# Power_Neg.net
KiCad netlist of a schematic drawn in Altium Designer
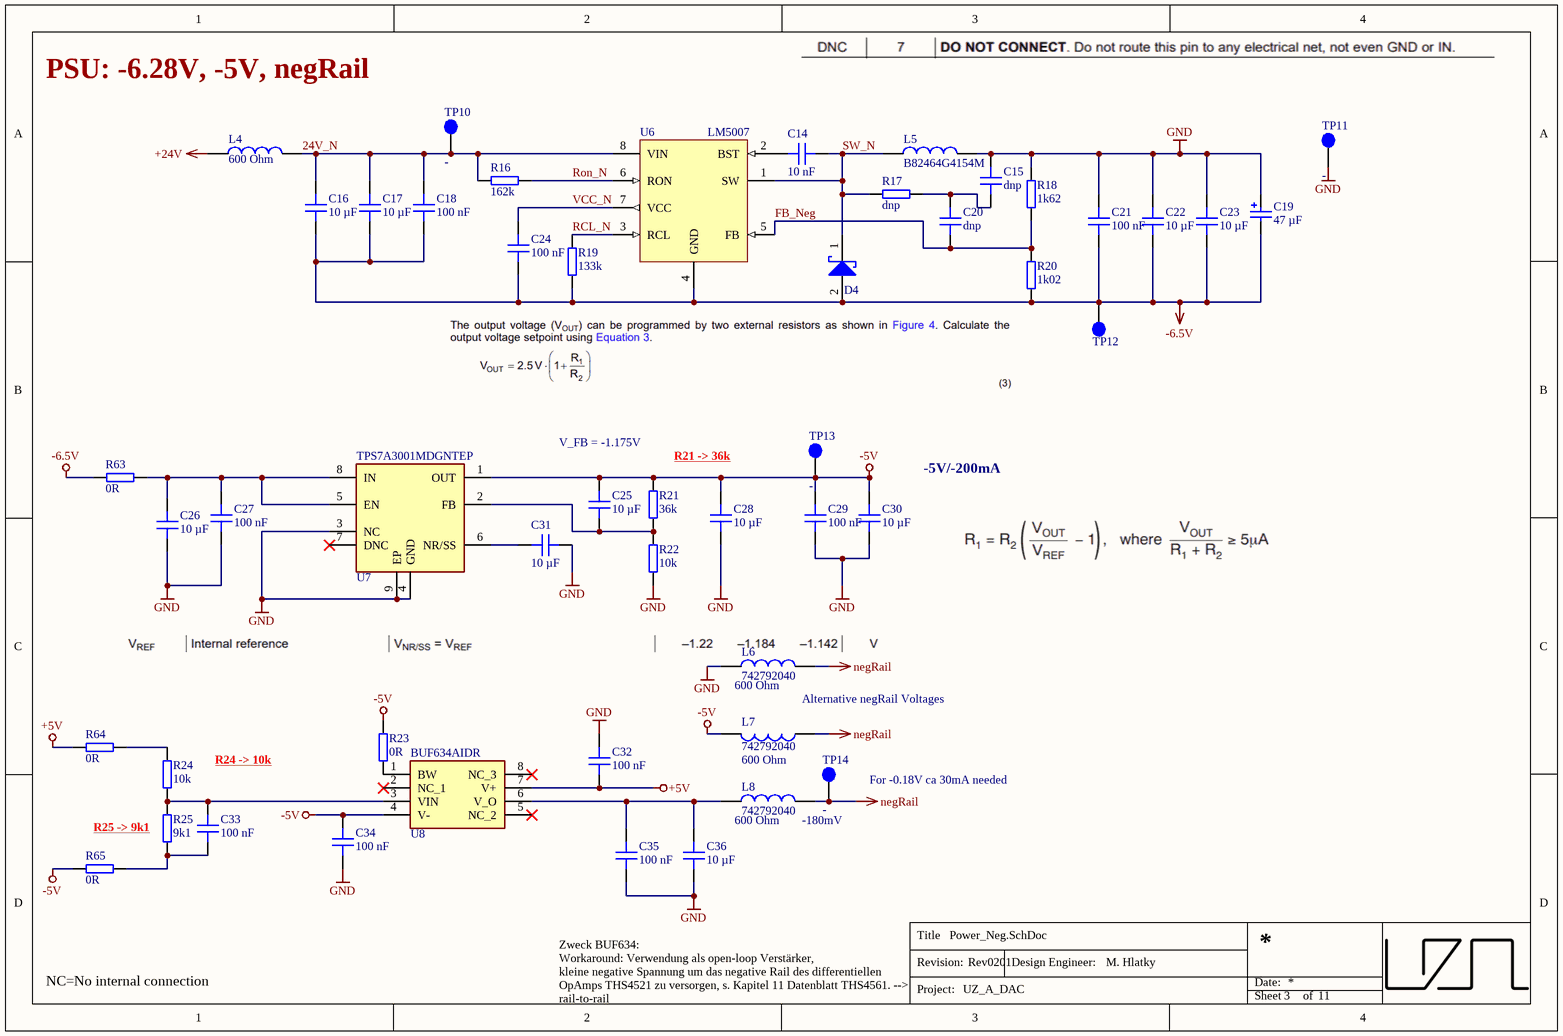
[diagram p0: Power_Neg.SchDoc]

(export (version "E")
  (design (tool "Eeschema 10.0.6"))
  (components
    (comp (ref "C14")
      (value "10 nF")
      (footprint "C_0603")
      (description "Capacitor 0603, 25 VDC, 10 nF, X7R")
      (fields
        (field (name "MANUFACTURER PART NUMBER") "885012206065")
        (field (name "MANUFACTURER") "Wurth Elektronik")
        (field (name "CREATED FROM") "MGremer")
      )
      (libsource (lib "user") (part "Capacitor"))
    )
    (comp (ref "C15")
      (value "dnp")
      (footprint "C_1206")
      (description "Capacitor 1206, 50 VDC, 0.027 µF, C0G")
      (fields
        (field (name "MANUFACTURER PART NUMBER") "GRM3195C1H273JA01D")
        (field (name "MANUFACTURER") "Murata Electronics")
        (field (name "CREATED FROM") "MGremer")
      )
      (libsource (lib "user") (part "Capacitor"))
    )
    (comp (ref "C16")
      (value "10 µF")
      (footprint "C_1206")
      (description "Capacitor 1206, 50 VDC, 10 µF, X5R")
      (fields
        (field (name "MANUFACTURER PART NUMBER") "GRT31CR61H106KE01L")
        (field (name "MANUFACTURER") "Murata Electronics")
        (field (name "CREATED FROM") "MGremer")
      )
      (libsource (lib "user") (part "Capacitor"))
    )
    (comp (ref "C17")
      (value "10 µF")
      (footprint "C_1206")
      (description "Capacitor 1206, 50 VDC, 10 µF, X5R")
      (fields
        (field (name "MANUFACTURER PART NUMBER") "GRT31CR61H106KE01L")
        (field (name "MANUFACTURER") "Murata Electronics")
        (field (name "CREATED FROM") "MGremer")
      )
      (libsource (lib "user") (part "Capacitor"))
    )
    (comp (ref "C18")
      (value "100 nF")
      (footprint "C_0603")
      (description "Capacitor 0603, 6.3 VDC, 100 nF, X5R")
      (fields
        (field (name "MANUFACTURER PART NUMBER") "C0603C104K9PACTU")
        (field (name "MANUFACTURER") "KEMET")
        (field (name "CREATED FROM") "MGremer")
      )
      (libsource (lib "user") (part "Capacitor"))
    )
    (comp (ref "C19")
      (value "47 µF")
      (footprint "WCAP-ASLI_5x5.5")
      (description "Capacitor WCAP, 6.3 VDC, 100 µF")
      (fields
        (field (name "MANUFACTURER PART NUMBER") "865080242004")
        (field (name "MANUFACTURER") "Wuerth Elektronik")
        (field (name "CREATED FROM") "MHlatky")
      )
      (libsource (lib "user") (part "Capacitor_Polarized"))
    )
    (comp (ref "C20")
      (value "dnp")
      (footprint "C_1206")
      (description "Capacitor 1206, 50 VDC, 0.027 µF, C0G")
      (fields
        (field (name "MANUFACTURER PART NUMBER") "GRM3195C1H273JA01D")
        (field (name "MANUFACTURER") "Murata Electronics")
        (field (name "CREATED FROM") "MGremer")
      )
      (libsource (lib "user") (part "Capacitor"))
    )
    (comp (ref "C21")
      (value "100 nF")
      (footprint "C_0603")
      (description "Capacitor 0603, 6.3 VDC, 100 nF, X5R")
      (fields
        (field (name "MANUFACTURER PART NUMBER") "C0603C104K9PACTU")
        (field (name "MANUFACTURER") "KEMET")
        (field (name "CREATED FROM") "MGremer")
      )
      (libsource (lib "user") (part "Capacitor"))
    )
    (comp (ref "C22")
      (value "10 µF")
      (footprint "C_1206")
      (description "Capacitor 1206, 50 VDC, 10 µF, X5R")
      (fields
        (field (name "MANUFACTURER PART NUMBER") "GRT31CR61H106KE01L")
        (field (name "MANUFACTURER") "Murata Electronics")
        (field (name "CREATED FROM") "MGremer")
      )
      (libsource (lib "user") (part "Capacitor"))
    )
    (comp (ref "C23")
      (value "10 µF")
      (footprint "C_1206")
      (description "Capacitor 1206, 50 VDC, 10 µF, X5R")
      (fields
        (field (name "MANUFACTURER PART NUMBER") "GRT31CR61H106KE01L")
        (field (name "MANUFACTURER") "Murata Electronics")
        (field (name "CREATED FROM") "MGremer")
      )
      (libsource (lib "user") (part "Capacitor"))
    )
    (comp (ref "C24")
      (value "100 nF")
      (footprint "C_0603")
      (description "Capacitor 0603, 6.3 VDC, 100 nF, X5R")
      (fields
        (field (name "MANUFACTURER PART NUMBER") "C0603C104K9PACTU")
        (field (name "MANUFACTURER") "KEMET")
        (field (name "CREATED FROM") "MGremer")
      )
      (libsource (lib "user") (part "Capacitor"))
    )
    (comp (ref "C25")
      (value "10 µF")
      (footprint "C_1206")
      (description "Capacitor 1206, 50 VDC, 10 µF, X5R")
      (fields
        (field (name "MANUFACTURER PART NUMBER") "GRT31CR61H106KE01L")
        (field (name "MANUFACTURER") "Murata Electronics")
        (field (name "CREATED FROM") "MGremer")
      )
      (libsource (lib "user") (part "Capacitor"))
    )
    (comp (ref "C26")
      (value "10 µF")
      (footprint "C_1206")
      (description "Capacitor 1206, 50 VDC, 10 µF, X5R")
      (fields
        (field (name "MANUFACTURER PART NUMBER") "GRT31CR61H106KE01L")
        (field (name "MANUFACTURER") "Murata Electronics")
        (field (name "CREATED FROM") "MGremer")
      )
      (libsource (lib "user") (part "Capacitor"))
    )
    (comp (ref "C27")
      (value "100 nF")
      (footprint "C_0603")
      (description "Capacitor 0603, 6.3 VDC, 100 nF, X5R")
      (fields
        (field (name "MANUFACTURER PART NUMBER") "C0603C104K9PACTU")
        (field (name "MANUFACTURER") "KEMET")
        (field (name "CREATED FROM") "MGremer")
      )
      (libsource (lib "user") (part "Capacitor"))
    )
    (comp (ref "C28")
      (value "10 µF")
      (footprint "C_1206")
      (description "Capacitor 1206, 50 VDC, 10 µF, X5R")
      (fields
        (field (name "MANUFACTURER PART NUMBER") "GRT31CR61H106KE01L")
        (field (name "MANUFACTURER") "Murata Electronics")
        (field (name "CREATED FROM") "MGremer")
      )
      (libsource (lib "user") (part "Capacitor"))
    )
    (comp (ref "C29")
      (value "100 nF")
      (footprint "C_0603")
      (description "Capacitor 0603, 6.3 VDC, 100 nF, X5R")
      (fields
        (field (name "MANUFACTURER PART NUMBER") "C0603C104K9PACTU")
        (field (name "MANUFACTURER") "KEMET")
        (field (name "CREATED FROM") "MGremer")
      )
      (libsource (lib "user") (part "Capacitor"))
    )
    (comp (ref "C30")
      (value "10 µF")
      (footprint "C_1206")
      (description "Capacitor 1206, 50 VDC, 10 µF, X5R")
      (fields
        (field (name "MANUFACTURER PART NUMBER") "GRT31CR61H106KE01L")
        (field (name "MANUFACTURER") "Murata Electronics")
        (field (name "CREATED FROM") "MGremer")
      )
      (libsource (lib "user") (part "Capacitor"))
    )
    (comp (ref "C31")
      (value "10 µF")
      (footprint "C_1206")
      (description "Capacitor 1206, 50 VDC, 10 µF, X5R")
      (fields
        (field (name "MANUFACTURER PART NUMBER") "GRT31CR61H106KE01L")
        (field (name "MANUFACTURER") "Murata Electronics")
        (field (name "CREATED FROM") "MGremer")
      )
      (libsource (lib "user") (part "Capacitor"))
    )
    (comp (ref "C32")
      (value "100 nF")
      (footprint "C_0603")
      (description "Capacitor 0603, 6.3 VDC, 100 nF, X5R")
      (fields
        (field (name "MANUFACTURER PART NUMBER") "C0603C104K9PACTU")
        (field (name "MANUFACTURER") "KEMET")
        (field (name "CREATED FROM") "MGremer")
      )
      (libsource (lib "user") (part "Capacitor"))
    )
    (comp (ref "C33")
      (value "100 nF")
      (footprint "C_0603")
      (description "Capacitor 0603, 6.3 VDC, 100 nF, X5R")
      (fields
        (field (name "MANUFACTURER PART NUMBER") "C0603C104K9PACTU")
        (field (name "MANUFACTURER") "KEMET")
        (field (name "CREATED FROM") "MGremer")
      )
      (libsource (lib "user") (part "Capacitor"))
    )
    (comp (ref "C34")
      (value "100 nF")
      (footprint "C_0603")
      (description "Capacitor 0603, 6.3 VDC, 100 nF, X5R")
      (fields
        (field (name "MANUFACTURER PART NUMBER") "C0603C104K9PACTU")
        (field (name "MANUFACTURER") "KEMET")
        (field (name "CREATED FROM") "MGremer")
      )
      (libsource (lib "user") (part "Capacitor"))
    )
    (comp (ref "C35")
      (value "100 nF")
      (footprint "C_0603")
      (description "Capacitor 0603, 6.3 VDC, 100 nF, X5R")
      (fields
        (field (name "MANUFACTURER PART NUMBER") "C0603C104K9PACTU")
        (field (name "MANUFACTURER") "KEMET")
        (field (name "CREATED FROM") "MGremer")
      )
      (libsource (lib "user") (part "Capacitor"))
    )
    (comp (ref "C36")
      (value "10 µF")
      (footprint "C_1206")
      (description "Capacitor 1206, 50 VDC, 10 µF, X5R")
      (fields
        (field (name "MANUFACTURER PART NUMBER") "GRT31CR61H106KE01L")
        (field (name "MANUFACTURER") "Murata Electronics")
        (field (name "CREATED FROM") "MGremer")
      )
      (libsource (lib "user") (part "Capacitor"))
    )
    (comp (ref "D4")
      (value "BYS12-90-E3/TR3")
      (footprint "DIOM4227X23N")
      (description "Schottky Rectifier, 1.5 A, 90 V")
      (fields
        (field (name "MANUFACTURER") "Vishay General Semiconductor")
        (field (name "CREATED FROM") "MGremer")
      )
      (libsource (lib "user") (part "STPS340-Y"))
    )
    (comp (ref "L4")
      (value "600 Ohm")
      (footprint "WE-CBF_0805_High Current")
      (description "Inductance, 0805, 100 MHz, 600 Ohm, 2 A")
      (fields
        (field (name "MANUFACTURER PART NUMBER") "742792040")
        (field (name "MANUFACTURER") "Wurth Elektronik")
        (field (name "CREATED FROM") "MGremer")
      )
      (libsource (lib "user") (part "WE-CBF"))
    )
    (comp (ref "L5")
      (value "B82464G4154M")
      (footprint "SMT_inductor_1050")
      (description "Inductor SMT, 10 x 10, 150 µH, 0.8 A")
      (fields
        (field (name "MF") "EPCOS / TDK")
        (field (name "MANUFACTURER") "TDK")
        (field (name "CREATED FROM") "MGremer")
      )
      (libsource (lib "user") (part "B82464G4154M"))
    )
    (comp (ref "L6")
      (value "742792040")
      (footprint "WE-CBF_0805_High Current")
      (description "Inductance, 0805, 100 MHz, 600 Ohm, 2 A")
      (fields
        (field (name "MANUFACTURER") "Wurth Elektronik")
        (field (name "ALTIUM_VALUE") "600 Ohm")
        (field (name "CREATED FROM") "MGremer")
      )
      (libsource (lib "user") (part "WE-CBF"))
    )
    (comp (ref "L7")
      (value "742792040")
      (footprint "WE-CBF_0805_High Current")
      (description "Inductance, 0805, 100 MHz, 600 Ohm, 2 A")
      (fields
        (field (name "MANUFACTURER") "Wurth Elektronik")
        (field (name "ALTIUM_VALUE") "600 Ohm")
        (field (name "CREATED FROM") "MGremer")
      )
      (libsource (lib "user") (part "WE-CBF"))
    )
    (comp (ref "L8")
      (value "742792040")
      (footprint "WE-CBF_0805_High Current")
      (description "Inductance, 0805, 100 MHz, 600 Ohm, 2 A")
      (fields
        (field (name "MANUFACTURER") "Wurth Elektronik")
        (field (name "ALTIUM_VALUE") "600 Ohm")
        (field (name "CREATED FROM") "MGremer")
      )
      (libsource (lib "user") (part "WE-CBF"))
    )
    (comp (ref "R16")
      (value "162k")
      (footprint "RES 0603_1608")
      (description "SMD resistor 1%")
      (fields
        (field (name "MANUFACTURER PART NUMBER") "CR0603-FX-1623ELF")
        (field (name "MANUFACTURER") "Burns")
        (field (name "CREATED FROM") "MGremer")
      )
      (libsource (lib "user") (part "Resistor"))
    )
    (comp (ref "R17")
      (value "dnp")
      (footprint "RES 0603_1608")
      (description "SMD resistor E24 series")
      (fields (field (name "CREATED FROM") "MGremer"))
      (libsource (lib "user") (part "Resistor"))
    )
    (comp (ref "R18")
      (value "1k62")
      (footprint "RES 0603_1608")
      (description "SMD resistor 1%")
      (fields
        (field (name "MANUFACTURER PART NUMBER") "ERJ-P03F1621V")
        (field (name "MANUFACTURER") "Panasonic")
        (field (name "CREATED FROM") "MGremer")
      )
      (libsource (lib "user") (part "Resistor"))
    )
    (comp (ref "R19")
      (value "133k")
      (footprint "RES 0603_1608")
      (description "SMD resistor 1%")
      (fields
        (field (name "MANUFACTURER PART NUMBER") "CR0603-FX-1333ELF")
        (field (name "MANUFACTURER") "Burns")
        (field (name "CREATED FROM") "MGremer")
      )
      (libsource (lib "user") (part "Resistor"))
    )
    (comp (ref "R20")
      (value "1k02")
      (footprint "RES 0603_1608")
      (description "SMD resistor 1%")
      (fields
        (field (name "MANUFACTURER PART NUMBER") "CR0603-FX-1021ELF")
        (field (name "MANUFACTURER") "Burns")
        (field (name "CREATED FROM") "MGremer")
      )
      (libsource (lib "user") (part "Resistor"))
    )
    (comp (ref "R21")
      (value "36k")
      (footprint "RES 0603_1608")
      (description "SMD resistor 1%")
      (fields
        (field (name "MANUFACTURER PART NUMBER") "RK73H1ETTP3602F")
        (field (name "MANUFACTURER") "KOA Speer")
        (field (name "CREATED FROM") "MHoerner")
      )
      (libsource (lib "user") (part "Resistor"))
    )
    (comp (ref "R22")
      (value "10k")
      (footprint "RES 0603_1608")
      (description "SMD resistor E24 series")
      (fields
        (field (name "MANUFACTURER PART NUMBER") "RK73B1JTTD103J")
        (field (name "MANUFACTURER") "KOA Speer")
        (field (name "CREATED FROM") "MGremer")
      )
      (libsource (lib "user") (part "Resistor"))
    )
    (comp (ref "R23")
      (value "0R")
      (footprint "RES 0603_1608")
      (description "SMD resistor E24 series")
      (fields
        (field (name "MANUFACTURER PART NUMBER") "RC0603JR-070RL")
        (field (name "MANUFACTURER") "YAGEO")
        (field (name "CREATED FROM") "MGremer")
      )
      (libsource (lib "user") (part "Resistor"))
    )
    (comp (ref "R24")
      (value "10k")
      (footprint "RES 0603_1608")
      (description "SMD resistor E24 series")
      (fields
        (field (name "MANUFACTURER PART NUMBER") "RK73B1JTTD103J")
        (field (name "MANUFACTURER") "KOA Speer")
        (field (name "CREATED FROM") "MGremer")
      )
      (libsource (lib "user") (part "Resistor"))
    )
    (comp (ref "R25")
      (value "9k1")
      (footprint "RES 0603_1608")
      (description "SMD resistor 1%")
      (fields
        (field (name "MANUFACTURER PART NUMBER") "SG73S1JTTD9101F")
        (field (name "MANUFACTURER") "KOA Speer")
        (field (name "CREATED FROM") "MHoerner")
      )
      (libsource (lib "user") (part "Resistor"))
    )
    (comp (ref "R63")
      (value "0R")
      (footprint "RES 0603_1608")
      (description "SMD resistor E24 series")
      (fields
        (field (name "MANUFACTURER PART NUMBER") "RC0603JR-070RL")
        (field (name "MANUFACTURER") "YAGEO")
        (field (name "CREATED FROM") "MGremer")
      )
      (libsource (lib "user") (part "Resistor"))
    )
    (comp (ref "R64")
      (value "0R")
      (footprint "RES 0603_1608")
      (description "SMD resistor E24 series")
      (fields
        (field (name "MANUFACTURER PART NUMBER") "RC0603JR-070RL")
        (field (name "MANUFACTURER") "YAGEO")
        (field (name "CREATED FROM") "MGremer")
      )
      (libsource (lib "user") (part "Resistor"))
    )
    (comp (ref "R65")
      (value "0R")
      (footprint "RES 0603_1608")
      (description "SMD resistor E24 series")
      (fields
        (field (name "MANUFACTURER PART NUMBER") "RC0603JR-070RL")
        (field (name "MANUFACTURER") "YAGEO")
        (field (name "CREATED FROM") "MGremer")
      )
      (libsource (lib "user") (part "Resistor"))
    )
    (comp (ref "TP10")
      (value "-")
      (footprint "TP_1mm")
      (description "Test Point 1 mm")
      (fields (field (name "CREATED") "2018_06_25_AGeiger") (field (name "CREATED FROM") "MGremer"))
      (libsource (lib "user") (part "TP_1mm"))
    )
    (comp (ref "TP11")
      (value "-")
      (footprint "TP_1mm")
      (description "Test Point 1 mm")
      (fields (field (name "CREATED") "2018_06_25_AGeiger") (field (name "CREATED FROM") "MGremer"))
      (libsource (lib "user") (part "TP_1mm"))
    )
    (comp (ref "TP12")
      (value "-")
      (footprint "TP_1mm")
      (description "Test Point 1 mm")
      (fields (field (name "CREATED") "2018_06_25_AGeiger") (field (name "CREATED FROM") "MGremer"))
      (libsource (lib "user") (part "TP_1mm"))
    )
    (comp (ref "TP13")
      (value "-")
      (footprint "TP_1mm")
      (description "Test Point 1 mm")
      (fields (field (name "CREATED") "2018_06_25_AGeiger") (field (name "CREATED FROM") "MGremer"))
      (libsource (lib "user") (part "TP_1mm"))
    )
    (comp (ref "TP14")
      (value "-")
      (footprint "TP_1mm")
      (description "Test Point 1 mm")
      (fields (field (name "CREATED") "2018_06_25_AGeiger") (field (name "CREATED FROM") "MGremer"))
      (libsource (lib "user") (part "TP_1mm"))
    )
    (comp (ref "U6")
      (value "LM5007MM/NOPB")
      (footprint "TSOP65P490X110-8N")
      (description "LM5007 75-V, 0.5-A DC/DC Buck Converter With 80-V Integrated Power MOSFET")
      (fields
        (field (name "MF") "Texas Instruments")
        (field (name "COMPONENT TYPE") "LM5007")
        (field (name "MANUFACTURER") "TI")
        (field (name "CREATED FROM") "MHlatky")
      )
      (libsource (lib "user") (part "LM5007"))
    )
    (comp (ref "U7")
      (value "TPS7A3001MDGNTEP")
      (footprint "SOP65P490X110-9N")
      (description "–36V, –200mA, ULTRALOW-NOISE, NEGATIVE LINEAR REGULATOR")
      (fields
        (field (name "MOUSER2 PART NUMBER") "595-TPS7A3001MDGNTEP")
        (field (name "MANUFACTURER") "TI")
        (field (name "CREATED FROM") "MHlatky")
      )
      (libsource (lib "user") (part "TPS7A3001MDGNTEP"))
    )
    (comp (ref "U8")
      (value "BUF634AIDR")
      (footprint "SOIC127P600X175-8N")
      (description "36-V, 210-MHz, 250-mA Output, High-Speed Buffer")
      (fields
        (field (name "MOUSER2 PART NUMBER") "595-BUF634AIDR")
        (field (name "MANUFACTURER") "TI")
        (field (name "CREATED FROM") "MHlatky")
      )
      (libsource (lib "user") (part "BUF634AIDR"))
    )
  )
  (nets
    (net (code "1") (name "+5V") (class "Default")
      (node (ref "C32") (pin "1") (pinfunction "1_1") (pintype "passive"))
      (node (ref "R64") (pin "1") (pinfunction "1_1") (pintype "passive"))
      (node (ref "U8") (pin "7") (pinfunction "V+_7") (pintype "passive"))
    )
    (net (code "2") (name "+24V") (class "Default")
      (node (ref "L4") (pin "1") (pinfunction "1_1") (pintype "passive"))
    )
    (net (code "3") (name "-5V") (class "Default")
      (node (ref "C25") (pin "2") (pinfunction "2_2") (pintype "passive"))
      (node (ref "C28") (pin "2") (pinfunction "2_2") (pintype "passive"))
      (node (ref "C29") (pin "2") (pinfunction "2_2") (pintype "passive"))
      (node (ref "C30") (pin "2") (pinfunction "2_2") (pintype "passive"))
      (node (ref "C34") (pin "2") (pinfunction "2_2") (pintype "passive"))
      (node (ref "L7") (pin "2") (pinfunction "2_2") (pintype "passive"))
      (node (ref "R21") (pin "2") (pinfunction "2_2") (pintype "passive"))
      (node (ref "R23") (pin "2") (pinfunction "2_2") (pintype "passive"))
      (node (ref "R65") (pin "1") (pinfunction "1_1") (pintype "passive"))
      (node (ref "TP13") (pin "1") (pintype "passive"))
      (node (ref "U7") (pin "1") (pinfunction "OUT_1") (pintype "passive"))
      (node (ref "U8") (pin "4") (pinfunction "V-_4") (pintype "passive"))
    )
    (net (code "4") (name "-6.5V") (class "Default")
      (node (ref "C16") (pin "1") (pinfunction "1_1") (pintype "passive"))
      (node (ref "C17") (pin "1") (pinfunction "1_1") (pintype "passive"))
      (node (ref "C18") (pin "1") (pinfunction "1_1") (pintype "passive"))
      (node (ref "C19") (pin "2") (pinfunction "N_2") (pintype "passive"))
      (node (ref "C21") (pin "1") (pinfunction "1_1") (pintype "passive"))
      (node (ref "C22") (pin "1") (pinfunction "1_1") (pintype "passive"))
      (node (ref "C23") (pin "1") (pinfunction "1_1") (pintype "passive"))
      (node (ref "C24") (pin "1") (pinfunction "1_1") (pintype "passive"))
      (node (ref "D4") (pin "2") (pinfunction "A_2") (pintype "passive"))
      (node (ref "R19") (pin "1") (pinfunction "1_1") (pintype "passive"))
      (node (ref "R20") (pin "1") (pinfunction "1_1") (pintype "passive"))
      (node (ref "R63") (pin "1") (pinfunction "1_1") (pintype "passive"))
      (node (ref "TP12") (pin "1") (pintype "passive"))
      (node (ref "U6") (pin "4") (pinfunction "GND_4") (pintype "power_in"))
    )
    (net (code "5") (name "/24V_N") (class "Default")
      (node (ref "C16") (pin "2") (pinfunction "2_2") (pintype "passive"))
      (node (ref "C17") (pin "2") (pinfunction "2_2") (pintype "passive"))
      (node (ref "C18") (pin "2") (pinfunction "2_2") (pintype "passive"))
      (node (ref "L4") (pin "2") (pinfunction "2_2") (pintype "passive"))
      (node (ref "R16") (pin "1") (pinfunction "1_1") (pintype "passive"))
      (node (ref "TP10") (pin "1") (pintype "passive"))
      (node (ref "U6") (pin "8") (pinfunction "VIN_8") (pintype "power_in"))
    )
    (net (code "6") (name "/FB_Neg") (class "Default")
      (node (ref "C20") (pin "1") (pinfunction "1_1") (pintype "passive"))
      (node (ref "R18") (pin "1") (pinfunction "1_1") (pintype "passive"))
      (node (ref "R20") (pin "2") (pinfunction "2_2") (pintype "passive"))
      (node (ref "U6") (pin "5") (pinfunction "FB_5") (pintype "input"))
    )
    (net (code "7") (name "/RCL_N") (class "Default")
      (node (ref "R19") (pin "2") (pinfunction "2_2") (pintype "passive"))
      (node (ref "U6") (pin "3") (pinfunction "RCL_3") (pintype "input"))
    )
    (net (code "8") (name "/Ron_N") (class "Default")
      (node (ref "R16") (pin "2") (pinfunction "2_2") (pintype "passive"))
      (node (ref "U6") (pin "6") (pinfunction "RON_6") (pintype "input"))
    )
    (net (code "9") (name "/SW_N") (class "Default")
      (node (ref "C14") (pin "2") (pinfunction "2_2") (pintype "passive"))
      (node (ref "D4") (pin "1") (pinfunction "K_1") (pintype "passive"))
      (node (ref "L5") (pin "1") (pinfunction "1_1") (pintype "passive"))
      (node (ref "R17") (pin "1") (pinfunction "1_1") (pintype "passive"))
      (node (ref "U6") (pin "1") (pinfunction "SW_1") (pintype "power_in"))
    )
    (net (code "10") (name "/VCC_N") (class "Default")
      (node (ref "C24") (pin "2") (pinfunction "2_2") (pintype "passive"))
      (node (ref "U6") (pin "7") (pinfunction "VCC_7") (pintype "output"))
    )
    (net (code "11") (name "GND") (class "Default")
      (node (ref "C15") (pin "2") (pinfunction "2_2") (pintype "passive"))
      (node (ref "C19") (pin "1") (pinfunction "P_1") (pintype "passive"))
      (node (ref "C21") (pin "2") (pinfunction "2_2") (pintype "passive"))
      (node (ref "C22") (pin "2") (pinfunction "2_2") (pintype "passive"))
      (node (ref "C23") (pin "2") (pinfunction "2_2") (pintype "passive"))
      (node (ref "C26") (pin "1") (pinfunction "1_1") (pintype "passive"))
      (node (ref "C27") (pin "1") (pinfunction "1_1") (pintype "passive"))
      (node (ref "C28") (pin "1") (pinfunction "1_1") (pintype "passive"))
      (node (ref "C29") (pin "1") (pinfunction "1_1") (pintype "passive"))
      (node (ref "C30") (pin "1") (pinfunction "1_1") (pintype "passive"))
      (node (ref "C31") (pin "1") (pinfunction "1_1") (pintype "passive"))
      (node (ref "C32") (pin "2") (pinfunction "2_2") (pintype "passive"))
      (node (ref "C34") (pin "1") (pinfunction "1_1") (pintype "passive"))
      (node (ref "C35") (pin "1") (pinfunction "1_1") (pintype "passive"))
      (node (ref "C36") (pin "1") (pinfunction "1_1") (pintype "passive"))
      (node (ref "L5") (pin "2") (pinfunction "2_2") (pintype "passive"))
      (node (ref "L6") (pin "1") (pinfunction "1_1") (pintype "passive"))
      (node (ref "R18") (pin "2") (pinfunction "2_2") (pintype "passive"))
      (node (ref "R22") (pin "1") (pinfunction "1_1") (pintype "passive"))
      (node (ref "TP11") (pin "1") (pintype "passive"))
      (node (ref "U7") (pin "3") (pinfunction "NC_3") (pintype "passive"))
      (node (ref "U7") (pin "4") (pinfunction "GND_4") (pintype "passive"))
      (node (ref "U7") (pin "9") (pinfunction "EP_9") (pintype "passive"))
    )
    (net (code "12") (name "Net-(C15-Pad1)") (class "Default")
      (node (ref "C15") (pin "1") (pinfunction "1_1") (pintype "passive"))
      (node (ref "C20") (pin "2") (pinfunction "2_2") (pintype "passive"))
      (node (ref "R17") (pin "2") (pinfunction "2_2") (pintype "passive"))
    )
    (net (code "13") (name "Net-(C33-Pad1)") (class "Default")
      (node (ref "C33") (pin "1") (pinfunction "1_1") (pintype "passive"))
      (node (ref "R25") (pin "1") (pinfunction "1_1") (pintype "passive"))
      (node (ref "R65") (pin "2") (pinfunction "2_2") (pintype "passive"))
    )
    (net (code "14") (name "Net-(R24-Pad2)") (class "Default")
      (node (ref "R24") (pin "2") (pinfunction "2_2") (pintype "passive"))
      (node (ref "R64") (pin "2") (pinfunction "2_2") (pintype "passive"))
    )
    (net (code "15") (name "Net-(U6-BST)") (class "Default")
      (node (ref "C14") (pin "1") (pinfunction "1_1") (pintype "passive"))
      (node (ref "U6") (pin "2") (pinfunction "BST_2") (pintype "input"))
    )
    (net (code "16") (name "Net-(U7-EN)") (class "Default")
      (node (ref "C26") (pin "2") (pinfunction "2_2") (pintype "passive"))
      (node (ref "C27") (pin "2") (pinfunction "2_2") (pintype "passive"))
      (node (ref "R63") (pin "2") (pinfunction "2_2") (pintype "passive"))
      (node (ref "U7") (pin "5") (pinfunction "EN_5") (pintype "passive"))
      (node (ref "U7") (pin "8") (pinfunction "IN_8") (pintype "passive"))
    )
    (net (code "17") (name "Net-(U7-FB)") (class "Default")
      (node (ref "C25") (pin "1") (pinfunction "1_1") (pintype "passive"))
      (node (ref "R21") (pin "1") (pinfunction "1_1") (pintype "passive"))
      (node (ref "R22") (pin "2") (pinfunction "2_2") (pintype "passive"))
      (node (ref "U7") (pin "2") (pinfunction "FB_2") (pintype "passive"))
    )
    (net (code "18") (name "Net-(U7-NR{slash}SS)") (class "Default")
      (node (ref "C31") (pin "2") (pinfunction "2_2") (pintype "passive"))
      (node (ref "U7") (pin "6") (pinfunction "NR/SS_6") (pintype "passive"))
    )
    (net (code "19") (name "Net-(U8-BW)") (class "Default")
      (node (ref "R23") (pin "1") (pinfunction "1_1") (pintype "passive"))
      (node (ref "U8") (pin "1") (pinfunction "BW_1") (pintype "passive"))
    )
    (net (code "20") (name "Net-(U8-VIN)") (class "Default")
      (node (ref "C33") (pin "2") (pinfunction "2_2") (pintype "passive"))
      (node (ref "R24") (pin "1") (pinfunction "1_1") (pintype "passive"))
      (node (ref "R25") (pin "2") (pinfunction "2_2") (pintype "passive"))
      (node (ref "U8") (pin "3") (pinfunction "VIN_3") (pintype "passive"))
    )
    (net (code "21") (name "Net-(U8-V_O)") (class "Default")
      (node (ref "C35") (pin "2") (pinfunction "2_2") (pintype "passive"))
      (node (ref "C36") (pin "2") (pinfunction "2_2") (pintype "passive"))
      (node (ref "L8") (pin "1") (pinfunction "1_1") (pintype "passive"))
      (node (ref "U8") (pin "6") (pinfunction "V_O_6") (pintype "passive"))
    )
    (net (code "22") (name "negRail") (class "Default")
      (node (ref "L6") (pin "2") (pinfunction "2_2") (pintype "passive"))
      (node (ref "L7") (pin "1") (pinfunction "1_1") (pintype "passive"))
      (node (ref "L8") (pin "2") (pinfunction "2_2") (pintype "passive"))
      (node (ref "TP14") (pin "1") (pintype "passive"))
    )
    (net (code "23") (name "unconnected-(U7-DNC-Pad7)") (class "Default")
      (node (ref "U7") (pin "7") (pinfunction "DNC_7") (pintype "passive+no_connect"))
    )
    (net (code "24") (name "unconnected-(U8-NC_1-Pad2)") (class "Default")
      (node (ref "U8") (pin "2") (pinfunction "NC_1_2") (pintype "passive+no_connect"))
    )
    (net (code "25") (name "unconnected-(U8-NC_2-Pad5)") (class "Default")
      (node (ref "U8") (pin "5") (pinfunction "NC_2_5") (pintype "passive+no_connect"))
    )
    (net (code "26") (name "unconnected-(U8-NC_3-Pad8)") (class "Default")
      (node (ref "U8") (pin "8") (pinfunction "NC_3_8") (pintype "passive+no_connect"))
    )
  )
)
